# MIPI_CSI-2.net
KiCad netlist of a schematic drawn in Altium Designer
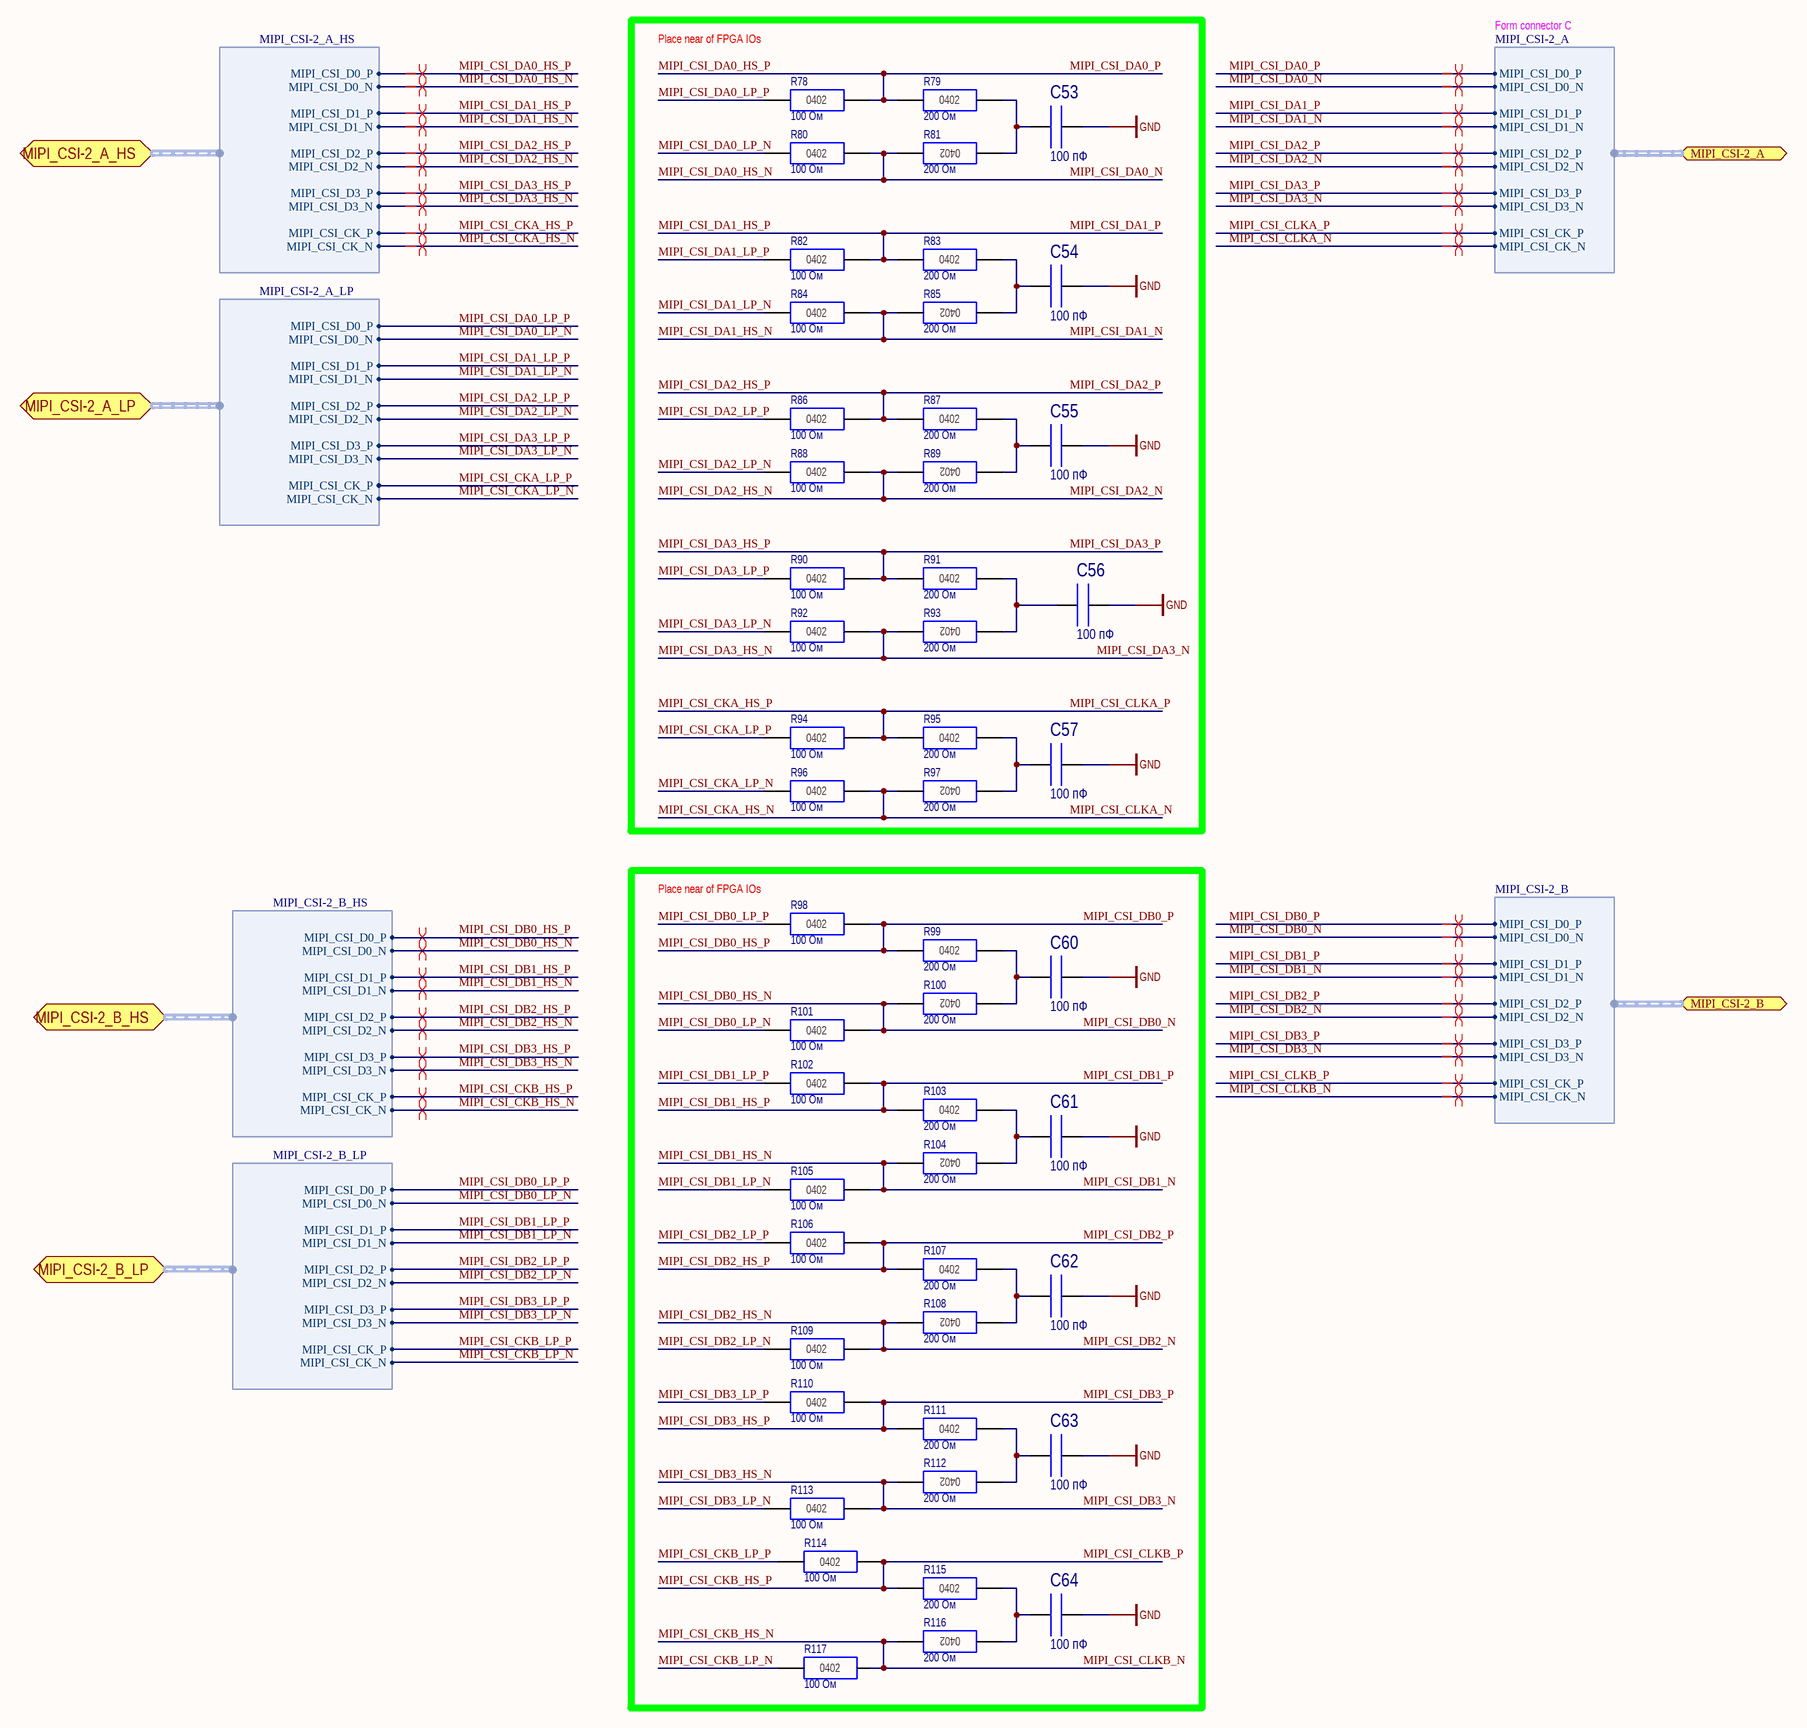
[diagram p0: MIPI_CSI-2.SchDoc]

(export (version "E")
  (design (tool "Eeschema 10.0.6"))
  (components
    (comp (ref "C53")
      (value "100 пФ")
      (footprint "CC0402(1005)_OCT")
      (description "Чип конденсатор керамический")
      (fields (field (name "Comment") "CC0402-NP0-100 пФ-1%-50В"))
      (libsource (lib "Чип конденсаторы") (part "CC0402-X7R-#-20%-10В"))
    )
    (comp (ref "C54")
      (value "100 пФ")
      (footprint "CC0402(1005)_OCT")
      (description "Чип конденсатор керамический")
      (fields (field (name "Comment") "CC0402-NP0-100 пФ-1%-50В"))
      (libsource (lib "Чип конденсаторы") (part "CC0402-X7R-#-20%-10В"))
    )
    (comp (ref "C55")
      (value "100 пФ")
      (footprint "CC0402(1005)_OCT")
      (description "Чип конденсатор керамический")
      (fields (field (name "Comment") "CC0402-NP0-100 пФ-1%-50В"))
      (libsource (lib "Чип конденсаторы") (part "CC0402-X7R-#-20%-10В"))
    )
    (comp (ref "C56")
      (value "100 пФ")
      (footprint "CC0402(1005)_OCT")
      (description "Чип конденсатор керамический")
      (fields (field (name "Comment") "CC0402-NP0-100 пФ-1%-50В"))
      (libsource (lib "Чип конденсаторы") (part "CC0402-X7R-#-20%-10В"))
    )
    (comp (ref "C57")
      (value "100 пФ")
      (footprint "CC0402(1005)_OCT")
      (description "Чип конденсатор керамический")
      (fields (field (name "Comment") "CC0402-NP0-100 пФ-1%-50В"))
      (libsource (lib "Чип конденсаторы") (part "CC0402-X7R-#-20%-10В"))
    )
    (comp (ref "C60")
      (value "100 пФ")
      (footprint "CC0402(1005)")
      (description "Чип конденсатор керамический")
      (fields (field (name "Comment") "CC0402-NP0-100 пФ-1%-50В"))
      (libsource (lib "Чип конденсаторы") (part "CC0402-X7R-#-20%-10В"))
    )
    (comp (ref "C61")
      (value "100 пФ")
      (footprint "CC0402(1005)")
      (description "Чип конденсатор керамический")
      (fields (field (name "Comment") "CC0402-NP0-100 пФ-1%-50В"))
      (libsource (lib "Чип конденсаторы") (part "CC0402-X7R-#-20%-10В"))
    )
    (comp (ref "C62")
      (value "100 пФ")
      (footprint "CC0402(1005)")
      (description "Чип конденсатор керамический")
      (fields (field (name "Comment") "CC0402-NP0-100 пФ-1%-50В"))
      (libsource (lib "Чип конденсаторы") (part "CC0402-X7R-#-20%-10В"))
    )
    (comp (ref "C63")
      (value "100 пФ")
      (footprint "CC0402(1005)")
      (description "Чип конденсатор керамический")
      (fields (field (name "Comment") "CC0402-NP0-100 пФ-1%-50В"))
      (libsource (lib "Чип конденсаторы") (part "CC0402-X7R-#-20%-10В"))
    )
    (comp (ref "C64")
      (value "100 пФ")
      (footprint "CC0402(1005)")
      (description "Чип конденсатор керамический")
      (fields (field (name "Comment") "CC0402-NP0-100 пФ-1%-50В"))
      (libsource (lib "Чип конденсаторы") (part "CC0402-X7R-#-20%-10В"))
    )
    (comp (ref "R78")
      (value "100 Ом")
      (footprint "CR0402(1005)_OCT")
      (description "Чип резистор")
      (fields (field (name "TOLERANCE") "5%") (field (name "Comment") "CR0402-100 Ом-±5%"))
      (libsource (lib "Резисторы") (part "CR0402-#-±5%"))
    )
    (comp (ref "R79")
      (value "200 Ом")
      (footprint "CR0402(1005)_OCT")
      (description "Чип резистор")
      (fields (field (name "TOLERANCE") "5%") (field (name "Comment") "CR0402-200 Ом-±5%"))
      (libsource (lib "Резисторы") (part "CR0402-#-±5%"))
    )
    (comp (ref "R80")
      (value "100 Ом")
      (footprint "CR0402(1005)_OCT")
      (description "Чип резистор")
      (fields (field (name "TOLERANCE") "5%") (field (name "Comment") "CR0402-100 Ом-±5%"))
      (libsource (lib "Резисторы") (part "CR0402-#-±5%"))
    )
    (comp (ref "R81")
      (value "200 Ом")
      (footprint "CR0402(1005)_OCT")
      (description "Чип резистор")
      (fields (field (name "TOLERANCE") "5%") (field (name "Comment") "CR0402-200 Ом-±5%"))
      (libsource (lib "") (part "CR0402-#-±5%_1"))
    )
    (comp (ref "R82")
      (value "100 Ом")
      (footprint "CR0402(1005)_OCT")
      (description "Чип резистор")
      (fields (field (name "TOLERANCE") "5%") (field (name "Comment") "CR0402-100 Ом-±5%"))
      (libsource (lib "Резисторы") (part "CR0402-#-±5%"))
    )
    (comp (ref "R83")
      (value "200 Ом")
      (footprint "CR0402(1005)_OCT")
      (description "Чип резистор")
      (fields (field (name "TOLERANCE") "5%") (field (name "Comment") "CR0402-200 Ом-±5%"))
      (libsource (lib "Резисторы") (part "CR0402-#-±5%"))
    )
    (comp (ref "R84")
      (value "100 Ом")
      (footprint "CR0402(1005)_OCT")
      (description "Чип резистор")
      (fields (field (name "TOLERANCE") "5%") (field (name "Comment") "CR0402-100 Ом-±5%"))
      (libsource (lib "Резисторы") (part "CR0402-#-±5%"))
    )
    (comp (ref "R85")
      (value "200 Ом")
      (footprint "CR0402(1005)_OCT")
      (description "Чип резистор")
      (fields (field (name "TOLERANCE") "5%") (field (name "Comment") "CR0402-200 Ом-±5%"))
      (libsource (lib "") (part "CR0402-#-±5%_1"))
    )
    (comp (ref "R86")
      (value "100 Ом")
      (footprint "CR0402(1005)_OCT")
      (description "Чип резистор")
      (fields (field (name "TOLERANCE") "5%") (field (name "Comment") "CR0402-100 Ом-±5%"))
      (libsource (lib "Резисторы") (part "CR0402-#-±5%"))
    )
    (comp (ref "R87")
      (value "200 Ом")
      (footprint "CR0402(1005)_OCT")
      (description "Чип резистор")
      (fields (field (name "TOLERANCE") "5%") (field (name "Comment") "CR0402-200 Ом-±5%"))
      (libsource (lib "Резисторы") (part "CR0402-#-±5%"))
    )
    (comp (ref "R88")
      (value "100 Ом")
      (footprint "CR0402(1005)_OCT")
      (description "Чип резистор")
      (fields (field (name "TOLERANCE") "5%") (field (name "Comment") "CR0402-100 Ом-±5%"))
      (libsource (lib "Резисторы") (part "CR0402-#-±5%"))
    )
    (comp (ref "R89")
      (value "200 Ом")
      (footprint "CR0402(1005)_OCT")
      (description "Чип резистор")
      (fields (field (name "TOLERANCE") "5%") (field (name "Comment") "CR0402-200 Ом-±5%"))
      (libsource (lib "") (part "CR0402-#-±5%_1"))
    )
    (comp (ref "R90")
      (value "100 Ом")
      (footprint "CR0402(1005)_OCT")
      (description "Чип резистор")
      (fields (field (name "TOLERANCE") "5%") (field (name "Comment") "CR0402-100 Ом-±5%"))
      (libsource (lib "Резисторы") (part "CR0402-#-±5%"))
    )
    (comp (ref "R91")
      (value "200 Ом")
      (footprint "CR0402(1005)_OCT")
      (description "Чип резистор")
      (fields (field (name "TOLERANCE") "5%") (field (name "Comment") "CR0402-200 Ом-±5%"))
      (libsource (lib "Резисторы") (part "CR0402-#-±5%"))
    )
    (comp (ref "R92")
      (value "100 Ом")
      (footprint "CR0402(1005)_OCT")
      (description "Чип резистор")
      (fields (field (name "TOLERANCE") "5%") (field (name "Comment") "CR0402-100 Ом-±5%"))
      (libsource (lib "Резисторы") (part "CR0402-#-±5%"))
    )
    (comp (ref "R93")
      (value "200 Ом")
      (footprint "CR0402(1005)_OCT")
      (description "Чип резистор")
      (fields (field (name "TOLERANCE") "5%") (field (name "Comment") "CR0402-200 Ом-±5%"))
      (libsource (lib "") (part "CR0402-#-±5%_1"))
    )
    (comp (ref "R94")
      (value "100 Ом")
      (footprint "CR0402(1005)_OCT")
      (description "Чип резистор")
      (fields (field (name "TOLERANCE") "5%") (field (name "Comment") "CR0402-100 Ом-±5%"))
      (libsource (lib "Резисторы") (part "CR0402-#-±5%"))
    )
    (comp (ref "R95")
      (value "200 Ом")
      (footprint "CR0402(1005)_OCT")
      (description "Чип резистор")
      (fields (field (name "TOLERANCE") "5%") (field (name "Comment") "CR0402-200 Ом-±5%"))
      (libsource (lib "Резисторы") (part "CR0402-#-±5%"))
    )
    (comp (ref "R96")
      (value "100 Ом")
      (footprint "CR0402(1005)_OCT")
      (description "Чип резистор")
      (fields (field (name "TOLERANCE") "5%") (field (name "Comment") "CR0402-100 Ом-±5%"))
      (libsource (lib "Резисторы") (part "CR0402-#-±5%"))
    )
    (comp (ref "R97")
      (value "200 Ом")
      (footprint "CR0402(1005)_OCT")
      (description "Чип резистор")
      (fields (field (name "TOLERANCE") "5%") (field (name "Comment") "CR0402-200 Ом-±5%"))
      (libsource (lib "") (part "CR0402-#-±5%_1"))
    )
    (comp (ref "R98")
      (value "100 Ом")
      (footprint "CR0402(1005)")
      (description "Чип резистор")
      (fields (field (name "TOLERANCE") "5%") (field (name "Comment") "CR0402-100 Ом-±5%"))
      (libsource (lib "Резисторы") (part "CR0402-#-±5%"))
    )
    (comp (ref "R99")
      (value "200 Ом")
      (footprint "CR0402(1005)")
      (description "Чип резистор")
      (fields (field (name "TOLERANCE") "5%") (field (name "Comment") "CR0402-200 Ом-±5%"))
      (libsource (lib "Резисторы") (part "CR0402-#-±5%"))
    )
    (comp (ref "R100")
      (value "200 Ом")
      (footprint "CR0402(1005)")
      (description "Чип резистор")
      (fields (field (name "TOLERANCE") "5%") (field (name "Comment") "CR0402-200 Ом-±5%"))
      (libsource (lib "") (part "CR0402-#-±5%_1"))
    )
    (comp (ref "R101")
      (value "100 Ом")
      (footprint "CR0402(1005)")
      (description "Чип резистор")
      (fields (field (name "TOLERANCE") "5%") (field (name "Comment") "CR0402-100 Ом-±5%"))
      (libsource (lib "Резисторы") (part "CR0402-#-±5%"))
    )
    (comp (ref "R102")
      (value "100 Ом")
      (footprint "CR0402(1005)")
      (description "Чип резистор")
      (fields (field (name "TOLERANCE") "5%") (field (name "Comment") "CR0402-100 Ом-±5%"))
      (libsource (lib "Резисторы") (part "CR0402-#-±5%"))
    )
    (comp (ref "R103")
      (value "200 Ом")
      (footprint "CR0402(1005)")
      (description "Чип резистор")
      (fields (field (name "TOLERANCE") "5%") (field (name "Comment") "CR0402-200 Ом-±5%"))
      (libsource (lib "Резисторы") (part "CR0402-#-±5%"))
    )
    (comp (ref "R104")
      (value "200 Ом")
      (footprint "CR0402(1005)")
      (description "Чип резистор")
      (fields (field (name "TOLERANCE") "5%") (field (name "Comment") "CR0402-200 Ом-±5%"))
      (libsource (lib "") (part "CR0402-#-±5%_1"))
    )
    (comp (ref "R105")
      (value "100 Ом")
      (footprint "CR0402(1005)")
      (description "Чип резистор")
      (fields (field (name "TOLERANCE") "5%") (field (name "Comment") "CR0402-100 Ом-±5%"))
      (libsource (lib "Резисторы") (part "CR0402-#-±5%"))
    )
    (comp (ref "R106")
      (value "100 Ом")
      (footprint "CR0402(1005)")
      (description "Чип резистор")
      (fields (field (name "TOLERANCE") "5%") (field (name "Comment") "CR0402-100 Ом-±5%"))
      (libsource (lib "Резисторы") (part "CR0402-#-±5%"))
    )
    (comp (ref "R107")
      (value "200 Ом")
      (footprint "CR0402(1005)")
      (description "Чип резистор")
      (fields (field (name "TOLERANCE") "5%") (field (name "Comment") "CR0402-200 Ом-±5%"))
      (libsource (lib "Резисторы") (part "CR0402-#-±5%"))
    )
    (comp (ref "R108")
      (value "200 Ом")
      (footprint "CR0402(1005)")
      (description "Чип резистор")
      (fields (field (name "TOLERANCE") "5%") (field (name "Comment") "CR0402-200 Ом-±5%"))
      (libsource (lib "") (part "CR0402-#-±5%_1"))
    )
    (comp (ref "R109")
      (value "100 Ом")
      (footprint "CR0402(1005)")
      (description "Чип резистор")
      (fields (field (name "TOLERANCE") "5%") (field (name "Comment") "CR0402-100 Ом-±5%"))
      (libsource (lib "Резисторы") (part "CR0402-#-±5%"))
    )
    (comp (ref "R110")
      (value "100 Ом")
      (footprint "CR0402(1005)")
      (description "Чип резистор")
      (fields (field (name "TOLERANCE") "5%") (field (name "Comment") "CR0402-100 Ом-±5%"))
      (libsource (lib "Резисторы") (part "CR0402-#-±5%"))
    )
    (comp (ref "R111")
      (value "200 Ом")
      (footprint "CR0402(1005)")
      (description "Чип резистор")
      (fields (field (name "TOLERANCE") "5%") (field (name "Comment") "CR0402-200 Ом-±5%"))
      (libsource (lib "Резисторы") (part "CR0402-#-±5%"))
    )
    (comp (ref "R112")
      (value "200 Ом")
      (footprint "CR0402(1005)")
      (description "Чип резистор")
      (fields (field (name "TOLERANCE") "5%") (field (name "Comment") "CR0402-200 Ом-±5%"))
      (libsource (lib "") (part "CR0402-#-±5%_1"))
    )
    (comp (ref "R113")
      (value "100 Ом")
      (footprint "CR0402(1005)")
      (description "Чип резистор")
      (fields (field (name "TOLERANCE") "5%") (field (name "Comment") "CR0402-100 Ом-±5%"))
      (libsource (lib "Резисторы") (part "CR0402-#-±5%"))
    )
    (comp (ref "R114")
      (value "100 Ом")
      (footprint "CR0402(1005)")
      (description "Чип резистор")
      (fields (field (name "TOLERANCE") "5%") (field (name "Comment") "CR0402-100 Ом-±5%"))
      (libsource (lib "Резисторы") (part "CR0402-#-±5%"))
    )
    (comp (ref "R115")
      (value "200 Ом")
      (footprint "CR0402(1005)")
      (description "Чип резистор")
      (fields (field (name "TOLERANCE") "5%") (field (name "Comment") "CR0402-200 Ом-±5%"))
      (libsource (lib "Резисторы") (part "CR0402-#-±5%"))
    )
    (comp (ref "R116")
      (value "200 Ом")
      (footprint "CR0402(1005)")
      (description "Чип резистор")
      (fields (field (name "TOLERANCE") "5%") (field (name "Comment") "CR0402-200 Ом-±5%"))
      (libsource (lib "") (part "CR0402-#-±5%_1"))
    )
    (comp (ref "R117")
      (value "100 Ом")
      (footprint "CR0402(1005)")
      (description "Чип резистор")
      (fields (field (name "TOLERANCE") "5%") (field (name "Comment") "CR0402-100 Ом-±5%"))
      (libsource (lib "Резисторы") (part "CR0402-#-±5%"))
    )
  )
  (nets
    (net (code "7") (name "/MIPI_CSI_CKA_HS_N") (class "Default")
      (node (ref "R96") (pin "2") (pinfunction "-_2") (pintype "passive"))
      (node (ref "R97") (pin "2") (pinfunction "-_2") (pintype "passive"))
    )
    (net (code "8") (name "/MIPI_CSI_CKA_HS_P") (class "Default")
      (node (ref "R94") (pin "2") (pinfunction "-_2") (pintype "passive"))
      (node (ref "R95") (pin "1") (pinfunction "+_1") (pintype "passive"))
    )
    (net (code "9") (name "/MIPI_CSI_CKA_LP_N") (class "Default")
      (node (ref "R96") (pin "1") (pinfunction "+_1") (pintype "passive"))
    )
    (net (code "10") (name "/MIPI_CSI_CKA_LP_P") (class "Default")
      (node (ref "R94") (pin "1") (pinfunction "+_1") (pintype "passive"))
    )
    (net (code "11") (name "/MIPI_CSI_CKB_HS_N") (class "Default")
      (node (ref "R116") (pin "2") (pinfunction "-_2") (pintype "passive"))
      (node (ref "R117") (pin "2") (pinfunction "-_2") (pintype "passive"))
    )
    (net (code "12") (name "/MIPI_CSI_CKB_HS_P") (class "Default")
      (node (ref "R114") (pin "2") (pinfunction "-_2") (pintype "passive"))
      (node (ref "R115") (pin "1") (pinfunction "+_1") (pintype "passive"))
    )
    (net (code "13") (name "/MIPI_CSI_CKB_LP_N") (class "Default")
      (node (ref "R117") (pin "1") (pinfunction "+_1") (pintype "passive"))
    )
    (net (code "14") (name "/MIPI_CSI_CKB_LP_P") (class "Default")
      (node (ref "R114") (pin "1") (pinfunction "+_1") (pintype "passive"))
    )
    (net (code "15") (name "/MIPI_CSI_DA0_HS_N") (class "Default")
      (node (ref "R80") (pin "2") (pinfunction "-_2") (pintype "passive"))
      (node (ref "R81") (pin "2") (pinfunction "-_2") (pintype "passive"))
    )
    (net (code "16") (name "/MIPI_CSI_DA0_HS_P") (class "Default")
      (node (ref "R78") (pin "2") (pinfunction "-_2") (pintype "passive"))
      (node (ref "R79") (pin "1") (pinfunction "+_1") (pintype "passive"))
    )
    (net (code "17") (name "/MIPI_CSI_DA0_LP_N") (class "Default")
      (node (ref "R80") (pin "1") (pinfunction "+_1") (pintype "passive"))
    )
    (net (code "18") (name "/MIPI_CSI_DA0_LP_P") (class "Default")
      (node (ref "R78") (pin "1") (pinfunction "+_1") (pintype "passive"))
    )
    (net (code "19") (name "/MIPI_CSI_DA1_HS_N") (class "Default")
      (node (ref "R84") (pin "2") (pinfunction "-_2") (pintype "passive"))
      (node (ref "R85") (pin "2") (pinfunction "-_2") (pintype "passive"))
    )
    (net (code "20") (name "/MIPI_CSI_DA1_HS_P") (class "Default")
      (node (ref "R82") (pin "2") (pinfunction "-_2") (pintype "passive"))
      (node (ref "R83") (pin "1") (pinfunction "+_1") (pintype "passive"))
    )
    (net (code "21") (name "/MIPI_CSI_DA1_LP_N") (class "Default")
      (node (ref "R84") (pin "1") (pinfunction "+_1") (pintype "passive"))
    )
    (net (code "22") (name "/MIPI_CSI_DA1_LP_P") (class "Default")
      (node (ref "R82") (pin "1") (pinfunction "+_1") (pintype "passive"))
    )
    (net (code "23") (name "/MIPI_CSI_DA2_HS_N") (class "Default")
      (node (ref "R88") (pin "2") (pinfunction "-_2") (pintype "passive"))
      (node (ref "R89") (pin "2") (pinfunction "-_2") (pintype "passive"))
    )
    (net (code "24") (name "/MIPI_CSI_DA2_HS_P") (class "Default")
      (node (ref "R86") (pin "2") (pinfunction "-_2") (pintype "passive"))
      (node (ref "R87") (pin "1") (pinfunction "+_1") (pintype "passive"))
    )
    (net (code "25") (name "/MIPI_CSI_DA2_LP_N") (class "Default")
      (node (ref "R88") (pin "1") (pinfunction "+_1") (pintype "passive"))
    )
    (net (code "26") (name "/MIPI_CSI_DA2_LP_P") (class "Default")
      (node (ref "R86") (pin "1") (pinfunction "+_1") (pintype "passive"))
    )
    (net (code "27") (name "/MIPI_CSI_DA3_HS_N") (class "Default")
      (node (ref "R92") (pin "2") (pinfunction "-_2") (pintype "passive"))
      (node (ref "R93") (pin "2") (pinfunction "-_2") (pintype "passive"))
    )
    (net (code "28") (name "/MIPI_CSI_DA3_HS_P") (class "Default")
      (node (ref "R90") (pin "2") (pinfunction "-_2") (pintype "passive"))
      (node (ref "R91") (pin "1") (pinfunction "+_1") (pintype "passive"))
    )
    (net (code "29") (name "/MIPI_CSI_DA3_LP_N") (class "Default")
      (node (ref "R92") (pin "1") (pinfunction "+_1") (pintype "passive"))
    )
    (net (code "30") (name "/MIPI_CSI_DA3_LP_P") (class "Default")
      (node (ref "R90") (pin "1") (pinfunction "+_1") (pintype "passive"))
    )
    (net (code "31") (name "/MIPI_CSI_DB0_HS_N") (class "Default")
      (node (ref "R100") (pin "2") (pinfunction "-_2") (pintype "passive"))
      (node (ref "R101") (pin "2") (pinfunction "-_2") (pintype "passive"))
    )
    (net (code "32") (name "/MIPI_CSI_DB0_HS_P") (class "Default")
      (node (ref "R98") (pin "2") (pinfunction "-_2") (pintype "passive"))
      (node (ref "R99") (pin "1") (pinfunction "+_1") (pintype "passive"))
    )
    (net (code "33") (name "/MIPI_CSI_DB0_LP_N") (class "Default")
      (node (ref "R101") (pin "1") (pinfunction "+_1") (pintype "passive"))
    )
    (net (code "34") (name "/MIPI_CSI_DB0_LP_P") (class "Default")
      (node (ref "R98") (pin "1") (pinfunction "+_1") (pintype "passive"))
    )
    (net (code "35") (name "/MIPI_CSI_DB1_HS_N") (class "Default")
      (node (ref "R104") (pin "2") (pinfunction "-_2") (pintype "passive"))
      (node (ref "R105") (pin "2") (pinfunction "-_2") (pintype "passive"))
    )
    (net (code "36") (name "/MIPI_CSI_DB1_HS_P") (class "Default")
      (node (ref "R102") (pin "2") (pinfunction "-_2") (pintype "passive"))
      (node (ref "R103") (pin "1") (pinfunction "+_1") (pintype "passive"))
    )
    (net (code "37") (name "/MIPI_CSI_DB1_LP_N") (class "Default")
      (node (ref "R105") (pin "1") (pinfunction "+_1") (pintype "passive"))
    )
    (net (code "38") (name "/MIPI_CSI_DB1_LP_P") (class "Default")
      (node (ref "R102") (pin "1") (pinfunction "+_1") (pintype "passive"))
    )
    (net (code "39") (name "/MIPI_CSI_DB2_HS_N") (class "Default")
      (node (ref "R108") (pin "2") (pinfunction "-_2") (pintype "passive"))
      (node (ref "R109") (pin "2") (pinfunction "-_2") (pintype "passive"))
    )
    (net (code "40") (name "/MIPI_CSI_DB2_HS_P") (class "Default")
      (node (ref "R106") (pin "2") (pinfunction "-_2") (pintype "passive"))
      (node (ref "R107") (pin "1") (pinfunction "+_1") (pintype "passive"))
    )
    (net (code "41") (name "/MIPI_CSI_DB2_LP_N") (class "Default")
      (node (ref "R109") (pin "1") (pinfunction "+_1") (pintype "passive"))
    )
    (net (code "42") (name "/MIPI_CSI_DB2_LP_P") (class "Default")
      (node (ref "R106") (pin "1") (pinfunction "+_1") (pintype "passive"))
    )
    (net (code "43") (name "/MIPI_CSI_DB3_HS_N") (class "Default")
      (node (ref "R112") (pin "2") (pinfunction "-_2") (pintype "passive"))
      (node (ref "R113") (pin "2") (pinfunction "-_2") (pintype "passive"))
    )
    (net (code "44") (name "/MIPI_CSI_DB3_HS_P") (class "Default")
      (node (ref "R110") (pin "2") (pinfunction "-_2") (pintype "passive"))
      (node (ref "R111") (pin "1") (pinfunction "+_1") (pintype "passive"))
    )
    (net (code "45") (name "/MIPI_CSI_DB3_LP_N") (class "Default")
      (node (ref "R113") (pin "1") (pinfunction "+_1") (pintype "passive"))
    )
    (net (code "46") (name "/MIPI_CSI_DB3_LP_P") (class "Default")
      (node (ref "R110") (pin "1") (pinfunction "+_1") (pintype "passive"))
    )
    (net (code "53") (name "GND") (class "Default")
      (node (ref "C53") (pin "1") (pinfunction "+_1") (pintype "passive"))
      (node (ref "C54") (pin "1") (pinfunction "+_1") (pintype "passive"))
      (node (ref "C55") (pin "1") (pinfunction "+_1") (pintype "passive"))
      (node (ref "C56") (pin "1") (pinfunction "+_1") (pintype "passive"))
      (node (ref "C57") (pin "1") (pinfunction "+_1") (pintype "passive"))
      (node (ref "C60") (pin "1") (pinfunction "+_1") (pintype "passive"))
      (node (ref "C61") (pin "1") (pinfunction "+_1") (pintype "passive"))
      (node (ref "C62") (pin "1") (pinfunction "+_1") (pintype "passive"))
      (node (ref "C63") (pin "1") (pinfunction "+_1") (pintype "passive"))
      (node (ref "C64") (pin "1") (pinfunction "+_1") (pintype "passive"))
    )
    (net (code "54") (name "Net-(C53--)") (class "Default")
      (node (ref "C53") (pin "2") (pinfunction "-_2") (pintype "passive"))
      (node (ref "R79") (pin "2") (pinfunction "-_2") (pintype "passive"))
      (node (ref "R81") (pin "1") (pinfunction "+_1") (pintype "passive"))
    )
    (net (code "55") (name "Net-(C54--)") (class "Default")
      (node (ref "C54") (pin "2") (pinfunction "-_2") (pintype "passive"))
      (node (ref "R83") (pin "2") (pinfunction "-_2") (pintype "passive"))
      (node (ref "R85") (pin "1") (pinfunction "+_1") (pintype "passive"))
    )
    (net (code "56") (name "Net-(C55--)") (class "Default")
      (node (ref "C55") (pin "2") (pinfunction "-_2") (pintype "passive"))
      (node (ref "R87") (pin "2") (pinfunction "-_2") (pintype "passive"))
      (node (ref "R89") (pin "1") (pinfunction "+_1") (pintype "passive"))
    )
    (net (code "57") (name "Net-(C56--)") (class "Default")
      (node (ref "C56") (pin "2") (pinfunction "-_2") (pintype "passive"))
      (node (ref "R91") (pin "2") (pinfunction "-_2") (pintype "passive"))
      (node (ref "R93") (pin "1") (pinfunction "+_1") (pintype "passive"))
    )
    (net (code "58") (name "Net-(C57--)") (class "Default")
      (node (ref "C57") (pin "2") (pinfunction "-_2") (pintype "passive"))
      (node (ref "R95") (pin "2") (pinfunction "-_2") (pintype "passive"))
      (node (ref "R97") (pin "1") (pinfunction "+_1") (pintype "passive"))
    )
    (net (code "59") (name "Net-(C60--)") (class "Default")
      (node (ref "C60") (pin "2") (pinfunction "-_2") (pintype "passive"))
      (node (ref "R100") (pin "1") (pinfunction "+_1") (pintype "passive"))
      (node (ref "R99") (pin "2") (pinfunction "-_2") (pintype "passive"))
    )
    (net (code "60") (name "Net-(C61--)") (class "Default")
      (node (ref "C61") (pin "2") (pinfunction "-_2") (pintype "passive"))
      (node (ref "R103") (pin "2") (pinfunction "-_2") (pintype "passive"))
      (node (ref "R104") (pin "1") (pinfunction "+_1") (pintype "passive"))
    )
    (net (code "61") (name "Net-(C62--)") (class "Default")
      (node (ref "C62") (pin "2") (pinfunction "-_2") (pintype "passive"))
      (node (ref "R107") (pin "2") (pinfunction "-_2") (pintype "passive"))
      (node (ref "R108") (pin "1") (pinfunction "+_1") (pintype "passive"))
    )
    (net (code "62") (name "Net-(C63--)") (class "Default")
      (node (ref "C63") (pin "2") (pinfunction "-_2") (pintype "passive"))
      (node (ref "R111") (pin "2") (pinfunction "-_2") (pintype "passive"))
      (node (ref "R112") (pin "1") (pinfunction "+_1") (pintype "passive"))
    )
    (net (code "63") (name "Net-(C64--)") (class "Default")
      (node (ref "C64") (pin "2") (pinfunction "-_2") (pintype "passive"))
      (node (ref "R115") (pin "2") (pinfunction "-_2") (pintype "passive"))
      (node (ref "R116") (pin "1") (pinfunction "+_1") (pintype "passive"))
    )
  )
)
